# diode_test.net
KiCad netlist of a schematic drawn in EAGLE
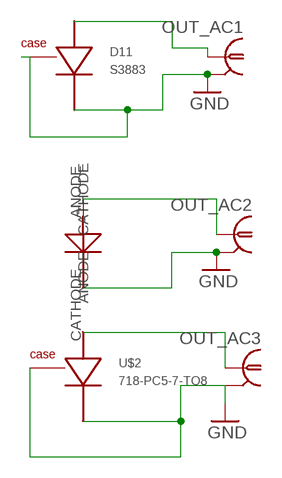
[diagram p0: schematic, sheet 1]

(export (version "E")
  (design (tool "Eeschema 10.0.6"))
  (components
    (comp (ref "D11")
      (value "S3883")
      (footprint "eagle-import:S3883-CASE")
      (libsource (lib "eagle-import") (part "S3883"))
    )
    (comp (ref "OUT_AC1")
      (value "BNC-H")
      (footprint "eagle-import:BNC90")
      (libsource (lib "eagle-import") (part "BNC-H"))
    )
    (comp (ref "OUT_AC2")
      (value "BNC-H")
      (footprint "eagle-import:BNC90")
      (libsource (lib "eagle-import") (part "BNC-H"))
    )
    (comp (ref "OUT_AC3")
      (value "BNC-H")
      (footprint "eagle-import:BNC90")
      (libsource (lib "eagle-import") (part "BNC-H"))
    )
    (comp (ref "U$1")
      (value "718-PC5-7-TO5")
      (footprint "eagle-import:718-PC5-7-TO5")
      (libsource (lib "eagle-import") (part "718-PC5-7-TO5"))
    )
    (comp (ref "U$2")
      (value "718-PC5-7-TO8")
      (footprint "eagle-import:718-PC5-7-TO8")
      (libsource (lib "eagle-import") (part "718-PC5-7-TO8"))
    )
  )
  (nets
    (net (code "1") (name "GND") (class "Default")
      (node (ref "D11") (pin "CASE") (pinfunction "CASE_CASE") (pintype "bidirectional"))
      (node (ref "D11") (pin "CATHODE") (pinfunction "CATHODE_CATHODE") (pintype "bidirectional"))
      (node (ref "OUT_AC1") (pin "2") (pinfunction "2_2") (pintype "passive"))
      (node (ref "OUT_AC2") (pin "2") (pinfunction "2_2") (pintype "passive"))
      (node (ref "OUT_AC3") (pin "2") (pinfunction "2_2") (pintype "passive"))
      (node (ref "U$1") (pin "CATHODE") (pinfunction "CATHODE_CATHODE") (pintype "bidirectional"))
      (node (ref "U$2") (pin "CASE") (pinfunction "CASE_CASE") (pintype "bidirectional"))
      (node (ref "U$2") (pin "CATHODE") (pinfunction "CATHODE_CATHODE") (pintype "bidirectional"))
    )
    (net (code "2") (name "Net-(D11-PadANODE)") (class "Default")
      (node (ref "D11") (pin "ANODE") (pinfunction "ANODE_ANODE") (pintype "bidirectional"))
      (node (ref "OUT_AC1") (pin "1") (pinfunction "1_1") (pintype "passive"))
    )
    (net (code "3") (name "Net-(OUT_AC2-Pad1)") (class "Default")
      (node (ref "OUT_AC2") (pin "1") (pinfunction "1_1") (pintype "passive"))
      (node (ref "U$1") (pin "ANODE") (pinfunction "ANODE_ANODE") (pintype "bidirectional"))
    )
    (net (code "4") (name "Net-(OUT_AC3-Pad1)") (class "Default")
      (node (ref "OUT_AC3") (pin "1") (pinfunction "1_1") (pintype "passive"))
      (node (ref "U$2") (pin "ANODE") (pinfunction "ANODE_ANODE") (pintype "bidirectional"))
    )
  )
)
